# XiaomiWeatherStation.net
KiCad netlist of a schematic drawn in EAGLE
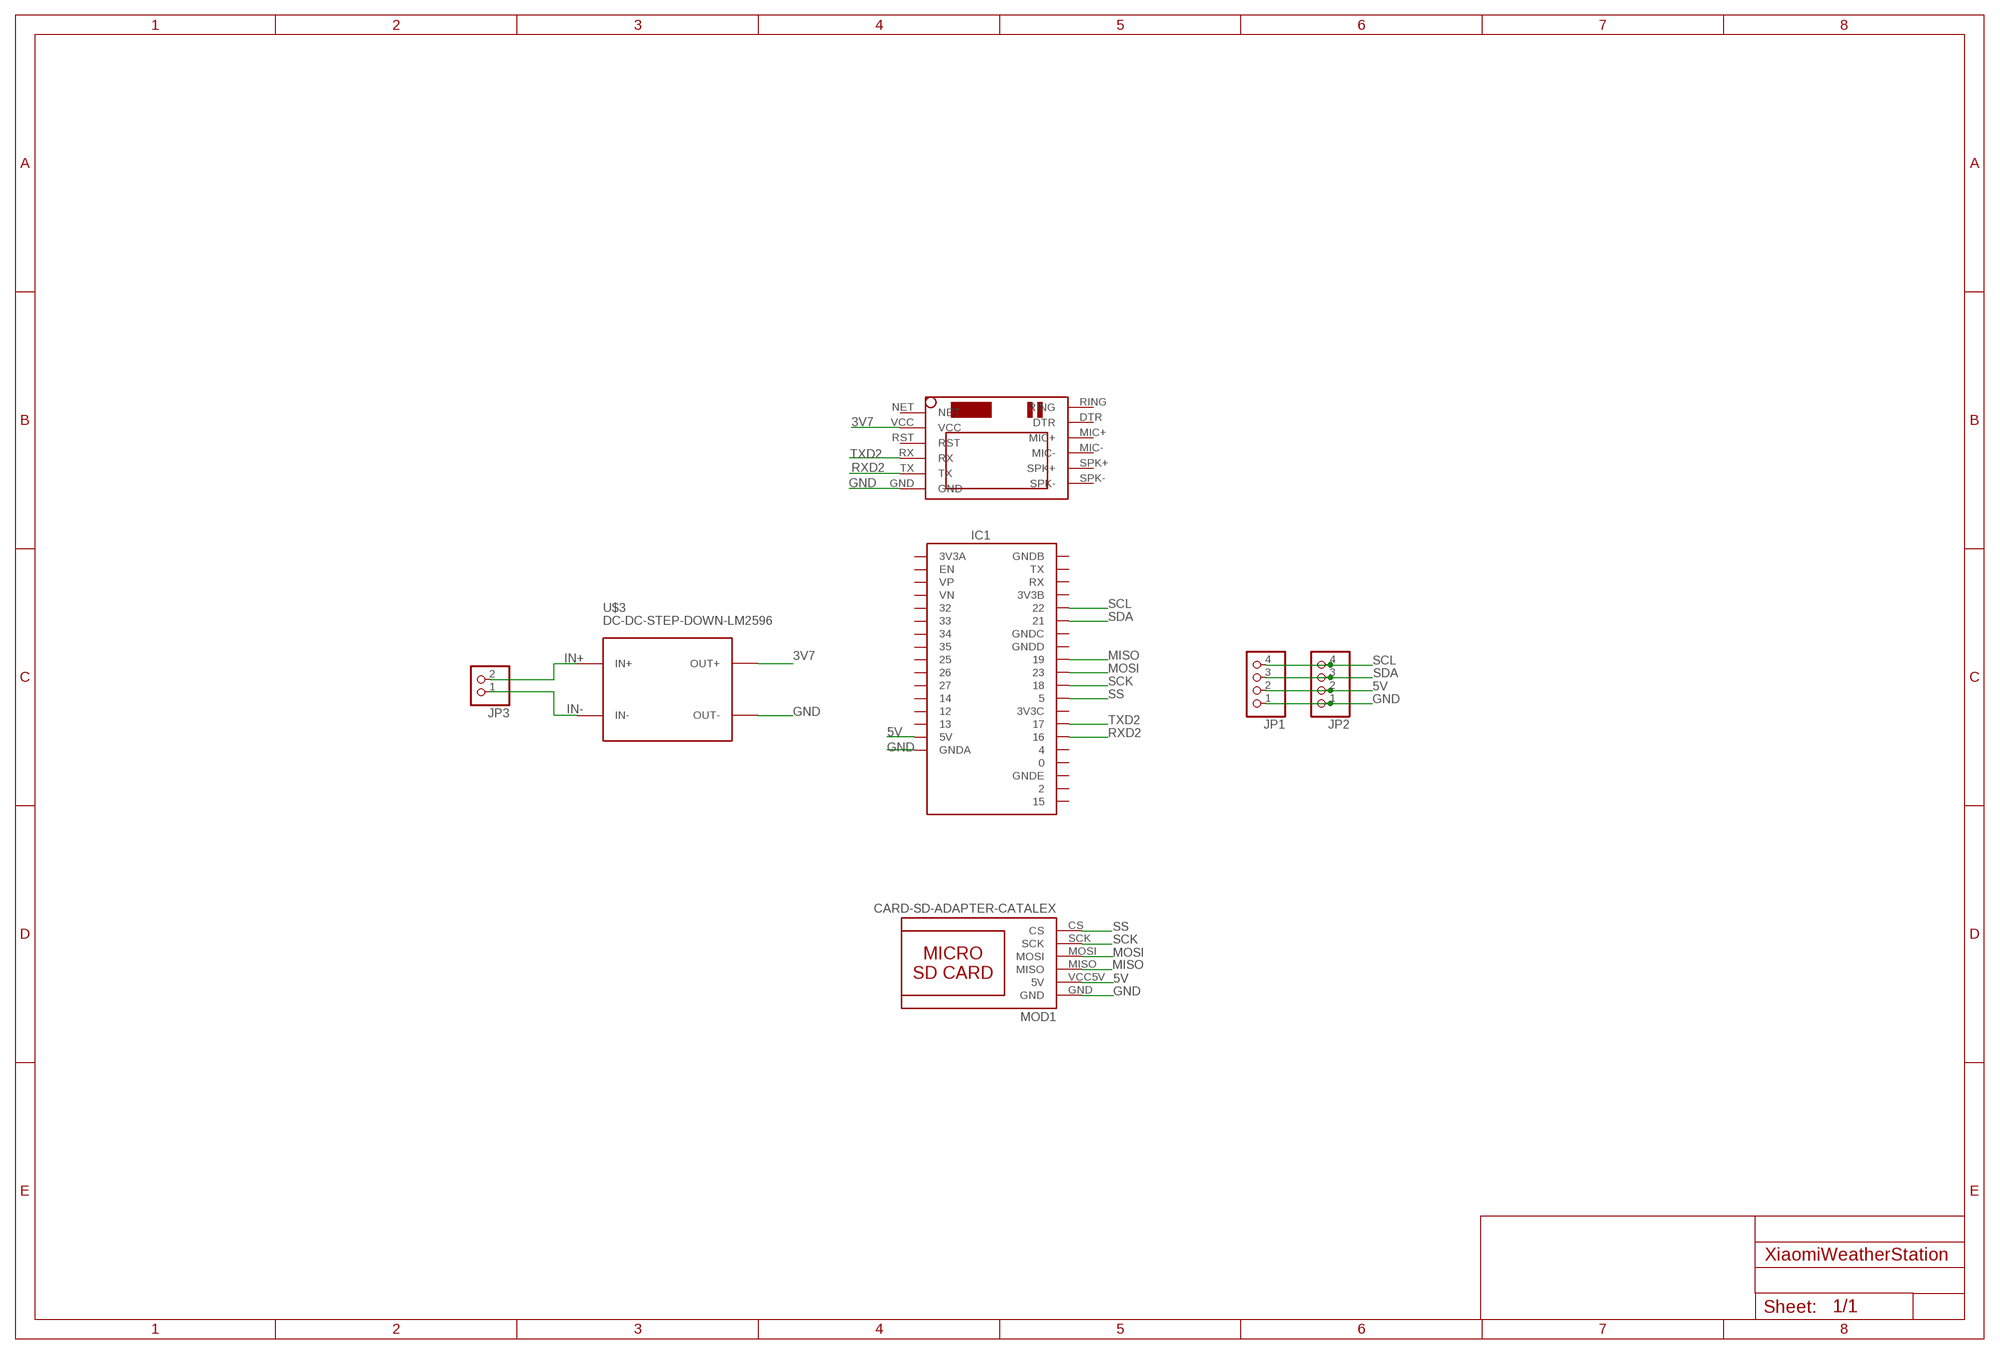
[diagram p0: schematic, sheet 1]

(export (version "E")
  (design (tool "Eeschema 10.0.6"))
  (components
    (comp (ref "IC1")
      (value "SSFD_LOLIN32_WEMOS_CHINA_W_BATT")
      (footprint "eagle-import:SSFD_LOLIN32_WEMOS_CHINA_W_BATT")
      (libsource (lib "eagle-import") (part "SSFD_LOLIN32_WEMOS_CHINA_W_BATT"))
    )
    (comp (ref "JP1")
      (value "PINHD-1X4")
      (footprint "eagle-import:1X04")
      (libsource (lib "eagle-import") (part "PINHD-1X4"))
    )
    (comp (ref "JP2")
      (value "PINHD-1X4")
      (footprint "eagle-import:1X04")
      (libsource (lib "eagle-import") (part "PINHD-1X4"))
    )
    (comp (ref "JP3")
      (value "PINHD-1X2")
      (footprint "eagle-import:1X02")
      (libsource (lib "eagle-import") (part "PINHD-1X2"))
    )
    (comp (ref "MOD1")
      (value "CARD-SD-ADAPTER-CATALEX")
      (footprint "eagle-import:CARD-SD-ADAPTER-CATALEX")
      (libsource (lib "eagle-import") (part "CARD-SD-ADAPTER-CATALEX"))
    )
    (comp (ref "U$1")
      (value "SIM800LMODULE")
      (footprint "eagle-import:SIM800LMODULE")
      (libsource (lib "eagle-import") (part "SIM800LMODULE"))
    )
    (comp (ref "U$3")
      (value "DC-DC-STEP-DOWN-LM2596")
      (footprint "eagle-import:DC-DC-STEP-DOWN-LM2596")
      (libsource (lib "eagle-import") (part "DC-DC-STEP-DOWN-LM2596"))
    )
  )
  (nets
    (net (code "1") (name "/3V7") (class "Default")
      (node (ref "U$1") (pin "VCC") (pinfunction "VCC_VCC") (pintype "bidirectional"))
      (node (ref "U$3") (pin "OUT+") (pinfunction "OUT+_OUT+") (pintype "bidirectional"))
    )
    (net (code "2") (name "/5V") (class "Default")
      (node (ref "IC1") (pin "5V") (pinfunction "5V_5V") (pintype "bidirectional"))
      (node (ref "JP1") (pin "2") (pinfunction "2_2") (pintype "passive"))
      (node (ref "JP2") (pin "2") (pinfunction "2_2") (pintype "passive"))
      (node (ref "MOD1") (pin "VCC5V") (pinfunction "5V_VCC5V") (pintype "power_in"))
    )
    (net (code "3") (name "/GND") (class "Default")
      (node (ref "IC1") (pin "GNDA") (pinfunction "GNDA_GNDA") (pintype "bidirectional"))
      (node (ref "JP1") (pin "1") (pinfunction "1_1") (pintype "passive"))
      (node (ref "JP2") (pin "1") (pinfunction "1_1") (pintype "passive"))
      (node (ref "MOD1") (pin "GND") (pinfunction "GND_GND") (pintype "power_in"))
      (node (ref "U$1") (pin "GND") (pinfunction "GND_GND") (pintype "bidirectional"))
      (node (ref "U$3") (pin "OUT-") (pinfunction "OUT-_OUT-") (pintype "bidirectional"))
    )
    (net (code "4") (name "/IN+") (class "Default")
      (node (ref "JP3") (pin "2") (pinfunction "2_2") (pintype "passive"))
      (node (ref "U$3") (pin "IN+") (pinfunction "IN+_IN+") (pintype "bidirectional"))
    )
    (net (code "5") (name "/IN-") (class "Default")
      (node (ref "JP3") (pin "1") (pinfunction "1_1") (pintype "passive"))
      (node (ref "U$3") (pin "IN-") (pinfunction "IN-_IN-") (pintype "bidirectional"))
    )
    (net (code "6") (name "/MISO") (class "Default")
      (node (ref "IC1") (pin "19") (pinfunction "19_19") (pintype "bidirectional"))
      (node (ref "MOD1") (pin "MISO") (pinfunction "MISO_MISO") (pintype "bidirectional"))
    )
    (net (code "7") (name "/MOSI") (class "Default")
      (node (ref "IC1") (pin "23") (pinfunction "23_23") (pintype "bidirectional"))
      (node (ref "MOD1") (pin "MOSI") (pinfunction "MOSI_MOSI") (pintype "bidirectional"))
    )
    (net (code "8") (name "/RXD2") (class "Default")
      (node (ref "IC1") (pin "16") (pinfunction "16_16") (pintype "bidirectional"))
      (node (ref "U$1") (pin "TX") (pinfunction "TX_TX") (pintype "bidirectional"))
    )
    (net (code "9") (name "/SCK") (class "Default")
      (node (ref "IC1") (pin "18") (pinfunction "18_18") (pintype "bidirectional"))
      (node (ref "MOD1") (pin "SCK") (pinfunction "SCK_SCK") (pintype "bidirectional"))
    )
    (net (code "10") (name "/SCL") (class "Default")
      (node (ref "IC1") (pin "22") (pinfunction "22_22") (pintype "bidirectional"))
      (node (ref "JP1") (pin "4") (pinfunction "4_4") (pintype "passive"))
      (node (ref "JP2") (pin "4") (pinfunction "4_4") (pintype "passive"))
    )
    (net (code "11") (name "/SDA") (class "Default")
      (node (ref "IC1") (pin "21") (pinfunction "21_21") (pintype "bidirectional"))
      (node (ref "JP1") (pin "3") (pinfunction "3_3") (pintype "passive"))
      (node (ref "JP2") (pin "3") (pinfunction "3_3") (pintype "passive"))
    )
    (net (code "12") (name "/SS") (class "Default")
      (node (ref "IC1") (pin "5") (pinfunction "5_5") (pintype "bidirectional"))
      (node (ref "MOD1") (pin "CS") (pinfunction "CS_CS") (pintype "bidirectional"))
    )
    (net (code "13") (name "/TXD2") (class "Default")
      (node (ref "IC1") (pin "17") (pinfunction "17_17") (pintype "bidirectional"))
      (node (ref "U$1") (pin "RX") (pinfunction "RX_RX") (pintype "bidirectional"))
    )
    (net (code "14") (name "unconnected-(IC1-Pad0)") (class "Default")
      (node (ref "IC1") (pin "0") (pinfunction "0_0") (pintype "bidirectional"))
    )
    (net (code "15") (name "unconnected-(IC1-Pad2)") (class "Default")
      (node (ref "IC1") (pin "2") (pinfunction "2_2") (pintype "bidirectional"))
    )
    (net (code "16") (name "unconnected-(IC1-Pad3V3A)") (class "Default")
      (node (ref "IC1") (pin "3V3A") (pinfunction "3V3A_3V3A") (pintype "bidirectional"))
    )
    (net (code "17") (name "unconnected-(IC1-Pad3V3B)") (class "Default")
      (node (ref "IC1") (pin "3V3B") (pinfunction "3V3B_3V3B") (pintype "bidirectional"))
    )
    (net (code "18") (name "unconnected-(IC1-Pad3V3C)") (class "Default")
      (node (ref "IC1") (pin "3V3C") (pinfunction "3V3C_3V3C") (pintype "bidirectional"))
    )
    (net (code "19") (name "unconnected-(IC1-Pad4)") (class "Default")
      (node (ref "IC1") (pin "4") (pinfunction "4_4") (pintype "bidirectional"))
    )
    (net (code "20") (name "unconnected-(IC1-Pad12)") (class "Default")
      (node (ref "IC1") (pin "12") (pinfunction "12_12") (pintype "bidirectional"))
    )
    (net (code "21") (name "unconnected-(IC1-Pad13)") (class "Default")
      (node (ref "IC1") (pin "13") (pinfunction "13_13") (pintype "bidirectional"))
    )
    (net (code "22") (name "unconnected-(IC1-Pad14)") (class "Default")
      (node (ref "IC1") (pin "14") (pinfunction "14_14") (pintype "bidirectional"))
    )
    (net (code "23") (name "unconnected-(IC1-Pad15)") (class "Default")
      (node (ref "IC1") (pin "15") (pinfunction "15_15") (pintype "bidirectional"))
    )
    (net (code "24") (name "unconnected-(IC1-Pad25)") (class "Default")
      (node (ref "IC1") (pin "25") (pinfunction "25_25") (pintype "bidirectional"))
    )
    (net (code "25") (name "unconnected-(IC1-Pad26)") (class "Default")
      (node (ref "IC1") (pin "26") (pinfunction "26_26") (pintype "bidirectional"))
    )
    (net (code "26") (name "unconnected-(IC1-Pad27)") (class "Default")
      (node (ref "IC1") (pin "27") (pinfunction "27_27") (pintype "bidirectional"))
    )
    (net (code "27") (name "unconnected-(IC1-Pad32)") (class "Default")
      (node (ref "IC1") (pin "32") (pinfunction "32_32") (pintype "bidirectional"))
    )
    (net (code "28") (name "unconnected-(IC1-Pad33)") (class "Default")
      (node (ref "IC1") (pin "33") (pinfunction "33_33") (pintype "bidirectional"))
    )
    (net (code "29") (name "unconnected-(IC1-Pad34)") (class "Default")
      (node (ref "IC1") (pin "34") (pinfunction "34_34") (pintype "bidirectional"))
    )
    (net (code "30") (name "unconnected-(IC1-Pad35)") (class "Default")
      (node (ref "IC1") (pin "35") (pinfunction "35_35") (pintype "bidirectional"))
    )
    (net (code "31") (name "unconnected-(IC1-PadEN)") (class "Default")
      (node (ref "IC1") (pin "EN") (pinfunction "EN_EN") (pintype "bidirectional"))
    )
    (net (code "32") (name "unconnected-(IC1-PadGNDB)") (class "Default")
      (node (ref "IC1") (pin "GNDB") (pinfunction "GNDB_GNDB") (pintype "bidirectional"))
    )
    (net (code "33") (name "unconnected-(IC1-PadGNDC)") (class "Default")
      (node (ref "IC1") (pin "GNDC") (pinfunction "GNDC_GNDC") (pintype "bidirectional"))
    )
    (net (code "34") (name "unconnected-(IC1-PadGNDD)") (class "Default")
      (node (ref "IC1") (pin "GNDD") (pinfunction "GNDD_GNDD") (pintype "bidirectional"))
    )
    (net (code "35") (name "unconnected-(IC1-PadGNDE)") (class "Default")
      (node (ref "IC1") (pin "GNDE") (pinfunction "GNDE_GNDE") (pintype "bidirectional"))
    )
    (net (code "36") (name "unconnected-(IC1-PadRX)") (class "Default")
      (node (ref "IC1") (pin "RX") (pinfunction "RX_RX") (pintype "bidirectional"))
    )
    (net (code "37") (name "unconnected-(IC1-PadTX)") (class "Default")
      (node (ref "IC1") (pin "TX") (pinfunction "TX_TX") (pintype "bidirectional"))
    )
    (net (code "38") (name "unconnected-(IC1-PadVN)") (class "Default")
      (node (ref "IC1") (pin "VN") (pinfunction "VN_VN") (pintype "bidirectional"))
    )
    (net (code "39") (name "unconnected-(IC1-PadVP)") (class "Default")
      (node (ref "IC1") (pin "VP") (pinfunction "VP_VP") (pintype "bidirectional"))
    )
    (net (code "40") (name "unconnected-(U$1-PadDTR)") (class "Default")
      (node (ref "U$1") (pin "DTR") (pinfunction "DTR_DTR") (pintype "bidirectional"))
    )
    (net (code "41") (name "unconnected-(U$1-PadMIC+)") (class "Default")
      (node (ref "U$1") (pin "MIC+") (pinfunction "MIC+_MIC+") (pintype "bidirectional"))
    )
    (net (code "42") (name "unconnected-(U$1-PadMIC-)") (class "Default")
      (node (ref "U$1") (pin "MIC-") (pinfunction "MIC-_MIC-") (pintype "bidirectional"))
    )
    (net (code "43") (name "unconnected-(U$1-PadNET)") (class "Default")
      (node (ref "U$1") (pin "NET") (pinfunction "NET_NET") (pintype "bidirectional"))
    )
    (net (code "44") (name "unconnected-(U$1-PadRING)") (class "Default")
      (node (ref "U$1") (pin "RING") (pinfunction "RING_RING") (pintype "bidirectional"))
    )
    (net (code "45") (name "unconnected-(U$1-PadRST)") (class "Default")
      (node (ref "U$1") (pin "RST") (pinfunction "RST_RST") (pintype "bidirectional"))
    )
    (net (code "46") (name "unconnected-(U$1-PadSPK+)") (class "Default")
      (node (ref "U$1") (pin "SPK+") (pinfunction "SPK+_SPK+") (pintype "bidirectional"))
    )
    (net (code "47") (name "unconnected-(U$1-PadSPK-)") (class "Default")
      (node (ref "U$1") (pin "SPK-") (pinfunction "SPK-_SPK-") (pintype "bidirectional"))
    )
  )
)
